# LTDC.net
KiCad netlist of a schematic drawn in Altium Designer
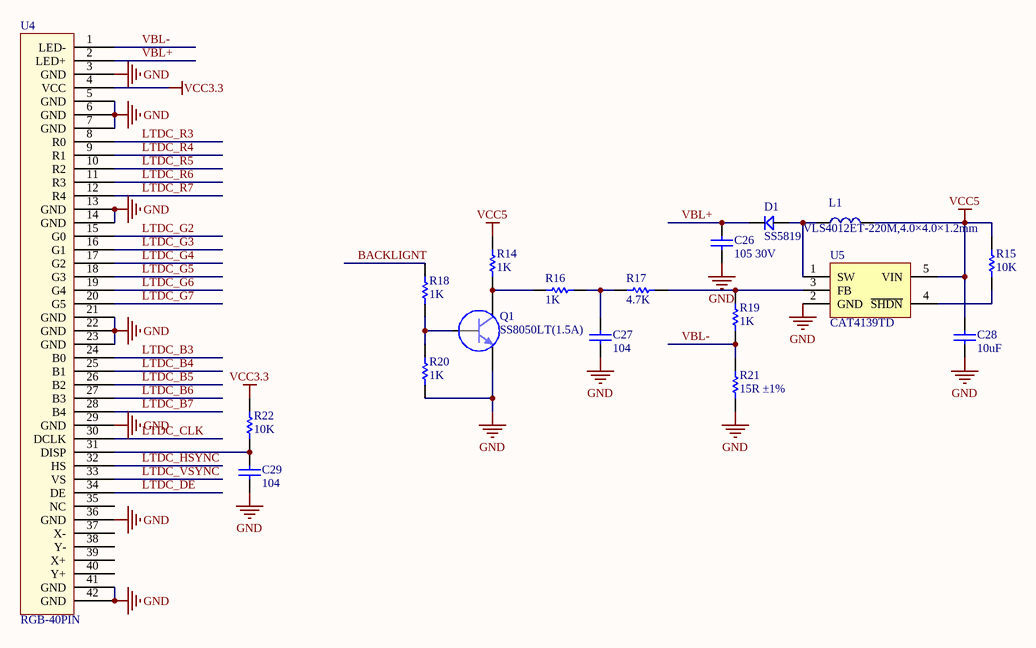
[diagram p0: LTDC.SchDoc]

(export (version "E")
  (design (tool "Eeschema 10.0.6"))
  (components
    (comp (ref "C26")
      (value "105 30V")
      (footprint "0603C")
      (description "电容")
      (libsource (lib "常用元件") (part "CAP-0603"))
    )
    (comp (ref "C27")
      (value "104")
      (footprint "0603C")
      (description "电容")
      (libsource (lib "常用元件") (part "CAP-0603"))
    )
    (comp (ref "C28")
      (value "10uF")
      (footprint "0603C")
      (description "电容")
      (libsource (lib "常用元件") (part "CAP-0603"))
    )
    (comp (ref "C29")
      (value "104")
      (footprint "0603C")
      (description "电容")
      (libsource (lib "常用元件") (part "CAP-0603"))
    )
    (comp (ref "D1") (value "SS5819") (footprint "SMA") (libsource (lib "常用元件") (part "1N4007")))
    (comp (ref "L1")
      (value "VLS4012ET-220M,4.0×4.0×1.2mm")
      (footprint "0603P")
      (libsource (lib "常用元件") (part "L"))
    )
    (comp (ref "Q1") (value "SS8050LT(1.5A)") (libsource (lib "常用元件") (part "S8050-R")))
    (comp (ref "R14")
      (value "1K")
      (footprint "0603R")
      (description "Resistance")
      (libsource (lib "常用元件") (part "RES-0603"))
    )
    (comp (ref "R15")
      (value "10K")
      (footprint "0603R")
      (description "Resistance")
      (libsource (lib "常用元件") (part "RES-0603"))
    )
    (comp (ref "R16")
      (value "1K")
      (footprint "0603R")
      (description "Resistance")
      (libsource (lib "常用元件") (part "RES-0603"))
    )
    (comp (ref "R17")
      (value "4.7K")
      (footprint "0603R")
      (description "Resistance")
      (libsource (lib "常用元件") (part "RES-0603"))
    )
    (comp (ref "R18")
      (value "1K")
      (footprint "0603R")
      (description "Resistance")
      (libsource (lib "常用元件") (part "RES-0603"))
    )
    (comp (ref "R19")
      (value "1K")
      (footprint "0603R")
      (description "Resistance")
      (libsource (lib "常用元件") (part "RES-0603"))
    )
    (comp (ref "R20")
      (value "1K")
      (footprint "0603R")
      (description "Resistance")
      (libsource (lib "常用元件") (part "RES-0603"))
    )
    (comp (ref "R21")
      (value "15R ±1%")
      (footprint "0603R")
      (description "Resistance")
      (libsource (lib "常用元件") (part "RES-0603"))
    )
    (comp (ref "R22")
      (value "10K")
      (footprint "0603R")
      (description "Resistance")
      (libsource (lib "常用元件") (part "RES-0603"))
    )
    (comp (ref "U4")
      (value "RGB-40PIN")
      (footprint "FPC40P_0.5MM")
      (description "40P通用液晶屏接口")
      (libsource (lib "常用元件") (part "RGB-40PIN"))
    )
    (comp (ref "U5") (value "CAT4139TD") (description "背光芯片") (libsource (lib "常用元件") (part "CAT4139TD")))
  )
  (nets
    (net (code "1") (name "/BACKLIGNT") (class "Default")
      (node (ref "R18") (pin "2") (pinfunction "2_2") (pintype "passive"))
    )
    (net (code "2") (name "/LTDC_B3") (class "Default")
      (node (ref "U4") (pin "24") (pinfunction "B0_24") (pintype "passive"))
    )
    (net (code "3") (name "/LTDC_B4") (class "Default")
      (node (ref "U4") (pin "25") (pinfunction "B1_25") (pintype "passive"))
    )
    (net (code "4") (name "/LTDC_B5") (class "Default")
      (node (ref "U4") (pin "26") (pinfunction "B2_26") (pintype "passive"))
    )
    (net (code "5") (name "/LTDC_B6") (class "Default")
      (node (ref "U4") (pin "27") (pinfunction "B3_27") (pintype "passive"))
    )
    (net (code "6") (name "/LTDC_B7") (class "Default")
      (node (ref "U4") (pin "28") (pinfunction "B4_28") (pintype "passive"))
    )
    (net (code "7") (name "/LTDC_CLK") (class "Default")
      (node (ref "U4") (pin "30") (pinfunction "DCLK_30") (pintype "passive"))
    )
    (net (code "8") (name "/LTDC_DE") (class "Default")
      (node (ref "U4") (pin "34") (pinfunction "DE_34") (pintype "passive"))
    )
    (net (code "9") (name "/LTDC_G2") (class "Default")
      (node (ref "U4") (pin "15") (pinfunction "G0_15") (pintype "passive"))
    )
    (net (code "10") (name "/LTDC_G3") (class "Default")
      (node (ref "U4") (pin "16") (pinfunction "G1_16") (pintype "passive"))
    )
    (net (code "11") (name "/LTDC_G4") (class "Default")
      (node (ref "U4") (pin "17") (pinfunction "G2_17") (pintype "passive"))
    )
    (net (code "12") (name "/LTDC_G5") (class "Default")
      (node (ref "U4") (pin "18") (pinfunction "G3_18") (pintype "passive"))
    )
    (net (code "13") (name "/LTDC_G6") (class "Default")
      (node (ref "U4") (pin "19") (pinfunction "G4_19") (pintype "passive"))
    )
    (net (code "14") (name "/LTDC_G7") (class "Default")
      (node (ref "U4") (pin "20") (pinfunction "G5_20") (pintype "passive"))
    )
    (net (code "15") (name "/LTDC_HSYNC") (class "Default")
      (node (ref "U4") (pin "32") (pinfunction "HS_32") (pintype "passive"))
    )
    (net (code "16") (name "/LTDC_R3") (class "Default")
      (node (ref "U4") (pin "8") (pinfunction "R0_8") (pintype "passive"))
    )
    (net (code "17") (name "/LTDC_R4") (class "Default")
      (node (ref "U4") (pin "9") (pinfunction "R1_9") (pintype "passive"))
    )
    (net (code "18") (name "/LTDC_R5") (class "Default")
      (node (ref "U4") (pin "10") (pinfunction "R2_10") (pintype "passive"))
    )
    (net (code "19") (name "/LTDC_R6") (class "Default")
      (node (ref "U4") (pin "11") (pinfunction "R3_11") (pintype "passive"))
    )
    (net (code "20") (name "/LTDC_R7") (class "Default")
      (node (ref "U4") (pin "12") (pinfunction "R4_12") (pintype "passive"))
    )
    (net (code "21") (name "/LTDC_VSYNC") (class "Default")
      (node (ref "U4") (pin "33") (pinfunction "VS_33") (pintype "passive"))
    )
    (net (code "22") (name "/VBL+") (class "Default")
      (node (ref "C26") (pin "2") (pinfunction "2_2") (pintype "passive"))
      (node (ref "D1") (pin "2") (pintype "passive"))
      (node (ref "U4") (pin "2") (pinfunction "LED+_2") (pintype "passive"))
    )
    (net (code "23") (name "/VBL-") (class "Default")
      (node (ref "R19") (pin "1") (pinfunction "1_1") (pintype "passive"))
      (node (ref "R21") (pin "2") (pinfunction "2_2") (pintype "passive"))
      (node (ref "U4") (pin "1") (pinfunction "LED-_1") (pintype "passive"))
    )
    (net (code "24") (name "GND") (class "Default")
      (node (ref "C26") (pin "1") (pinfunction "1_1") (pintype "passive"))
      (node (ref "C27") (pin "1") (pinfunction "1_1") (pintype "passive"))
      (node (ref "C28") (pin "1") (pinfunction "1_1") (pintype "passive"))
      (node (ref "C29") (pin "1") (pinfunction "1_1") (pintype "passive"))
      (node (ref "Q1") (pin "2") (pinfunction "E_2") (pintype "passive"))
      (node (ref "R20") (pin "1") (pinfunction "1_1") (pintype "passive"))
      (node (ref "R21") (pin "1") (pinfunction "1_1") (pintype "passive"))
      (node (ref "U4") (pin "13") (pinfunction "GND_13") (pintype "passive"))
      (node (ref "U4") (pin "14") (pinfunction "GND_14") (pintype "passive"))
      (node (ref "U4") (pin "21") (pinfunction "GND_21") (pintype "passive"))
      (node (ref "U4") (pin "22") (pinfunction "GND_22") (pintype "passive"))
      (node (ref "U4") (pin "23") (pinfunction "GND_23") (pintype "passive"))
      (node (ref "U4") (pin "29") (pinfunction "GND_29") (pintype "passive"))
      (node (ref "U4") (pin "3") (pinfunction "GND_3") (pintype "passive"))
      (node (ref "U4") (pin "36") (pinfunction "GND_36") (pintype "passive"))
      (node (ref "U4") (pin "41") (pinfunction "GND_41") (pintype "passive"))
      (node (ref "U4") (pin "42") (pinfunction "GND_42") (pintype "passive"))
      (node (ref "U4") (pin "5") (pinfunction "GND_5") (pintype "passive"))
      (node (ref "U4") (pin "6") (pinfunction "GND_6") (pintype "passive"))
      (node (ref "U4") (pin "7") (pinfunction "GND_7") (pintype "passive"))
      (node (ref "U5") (pin "2") (pinfunction "GND_2") (pintype "passive"))
    )
    (net (code "25") (name "Net-(C27-Pad2)") (class "Default")
      (node (ref "C27") (pin "2") (pinfunction "2_2") (pintype "passive"))
      (node (ref "R16") (pin "1") (pinfunction "1_1") (pintype "passive"))
      (node (ref "R17") (pin "1") (pinfunction "1_1") (pintype "passive"))
    )
    (net (code "26") (name "Net-(Q1-B)") (class "Default")
      (node (ref "Q1") (pin "1") (pinfunction "B_1") (pintype "passive"))
      (node (ref "R18") (pin "1") (pinfunction "1_1") (pintype "passive"))
      (node (ref "R20") (pin "2") (pinfunction "2_2") (pintype "passive"))
    )
    (net (code "27") (name "Net-(Q1-C)") (class "Default")
      (node (ref "Q1") (pin "3") (pinfunction "C_3") (pintype "passive"))
      (node (ref "R14") (pin "1") (pinfunction "1_1") (pintype "passive"))
      (node (ref "R16") (pin "2") (pinfunction "2_2") (pintype "passive"))
    )
    (net (code "28") (name "Net-(U4-DISP)") (class "Default")
      (node (ref "C29") (pin "2") (pinfunction "2_2") (pintype "passive"))
      (node (ref "R22") (pin "1") (pinfunction "1_1") (pintype "passive"))
      (node (ref "U4") (pin "31") (pinfunction "DISP_31") (pintype "passive"))
    )
    (net (code "29") (name "Net-(U5-FB)") (class "Default")
      (node (ref "R17") (pin "2") (pinfunction "2_2") (pintype "passive"))
      (node (ref "R19") (pin "2") (pinfunction "2_2") (pintype "passive"))
      (node (ref "U5") (pin "3") (pinfunction "FB_3") (pintype "passive"))
    )
    (net (code "30") (name "Net-(U5-SW)") (class "Default")
      (node (ref "D1") (pin "1") (pintype "passive"))
      (node (ref "L1") (pin "1") (pintype "passive"))
      (node (ref "U5") (pin "1") (pinfunction "SW_1") (pintype "passive"))
    )
    (net (code "31") (name "Net-(U5-~{SHDN})") (class "Default")
      (node (ref "R15") (pin "1") (pinfunction "1_1") (pintype "passive"))
      (node (ref "U5") (pin "4") (pinfunction "~{SHDN}_4") (pintype "passive"))
    )
    (net (code "32") (name "VCC3.3") (class "Default")
      (node (ref "R22") (pin "2") (pinfunction "2_2") (pintype "passive"))
      (node (ref "U4") (pin "4") (pinfunction "VCC_4") (pintype "passive"))
    )
    (net (code "33") (name "VCC5") (class "Default")
      (node (ref "C28") (pin "2") (pinfunction "2_2") (pintype "passive"))
      (node (ref "L1") (pin "2") (pintype "passive"))
      (node (ref "R14") (pin "2") (pinfunction "2_2") (pintype "passive"))
      (node (ref "R15") (pin "2") (pinfunction "2_2") (pintype "passive"))
      (node (ref "U5") (pin "5") (pinfunction "VIN_5") (pintype "passive"))
    )
    (net (code "34") (name "unconnected-(U4-NC-Pad35)") (class "Default")
      (node (ref "U4") (pin "35") (pinfunction "NC_35") (pintype "passive"))
    )
    (net (code "35") (name "unconnected-(U4-X+-Pad39)") (class "Default")
      (node (ref "U4") (pin "39") (pinfunction "X+_39") (pintype "passive"))
    )
    (net (code "36") (name "unconnected-(U4-X--Pad37)") (class "Default")
      (node (ref "U4") (pin "37") (pinfunction "X-_37") (pintype "passive"))
    )
    (net (code "37") (name "unconnected-(U4-Y+-Pad40)") (class "Default")
      (node (ref "U4") (pin "40") (pinfunction "Y+_40") (pintype "passive"))
    )
    (net (code "38") (name "unconnected-(U4-Y--Pad38)") (class "Default")
      (node (ref "U4") (pin "38") (pinfunction "Y-_38") (pintype "passive"))
    )
  )
)
